# montaj_board_v2_0.net
KiCad netlist of a schematic drawn in EAGLE
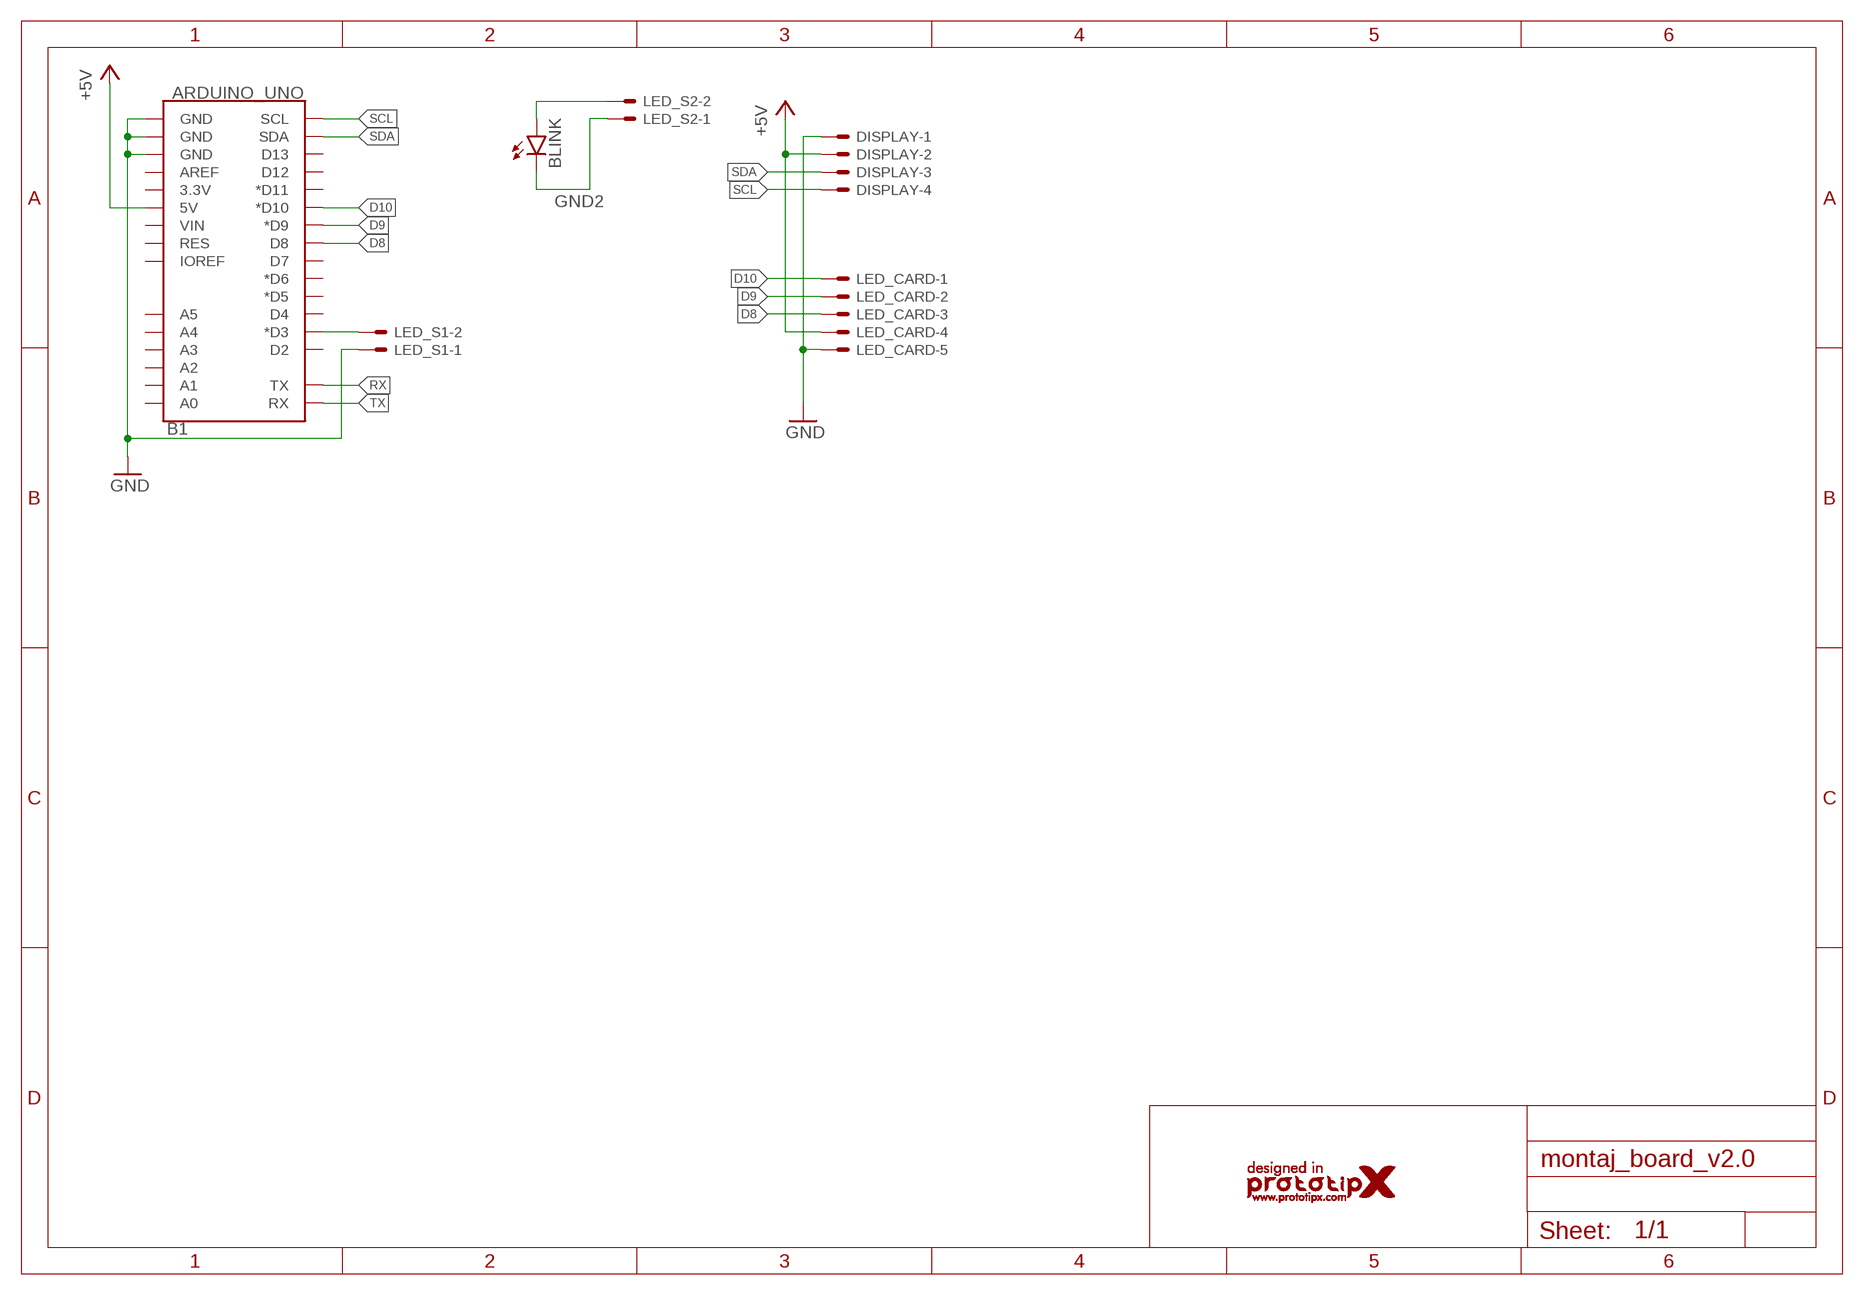
[diagram p0: schematic, sheet 1]

(export (version "E")
  (design (tool "Eeschema 10.0.6"))
  (components
    (comp (ref "B1")
      (value "ARDUINO_UNO")
      (footprint "eagle-import:UNO_R3_SHIELD")
      (libsource (lib "eagle-import") (part "ARDUINO_UNO_R3_SHIELDBASIC"))
    )
    (comp (ref "BLINK")
      (value "LED3MM")
      (footprint "eagle-import:LED3MM")
      (libsource (lib "eagle-import") (part "LED3MM"))
    )
    (comp (ref "DISPLAY")
      (value "C-GRID-04-70543")
      (footprint "eagle-import:70543-04")
      (fields (field (name "MF") "MOLEX"))
      (libsource (lib "eagle-import") (part "C-GRID-04-70543"))
    )
    (comp (ref "LED_CARD")
      (value "C-GRID-05-70543")
      (footprint "eagle-import:70543-05")
      (fields (field (name "MF") "MOLEX"))
      (libsource (lib "eagle-import") (part "C-GRID-05-70543"))
    )
    (comp (ref "LED_S1")
      (value "C-GRID-02-70543")
      (footprint "eagle-import:70543-02")
      (fields (field (name "MF") "MOLEX"))
      (libsource (lib "eagle-import") (part "C-GRID-02-70543"))
    )
    (comp (ref "LED_S2")
      (value "C-GRID-02-70543")
      (footprint "eagle-import:70543-02")
      (fields (field (name "MF") "MOLEX"))
      (libsource (lib "eagle-import") (part "C-GRID-02-70543"))
    )
    (comp (ref "LOGO1")
      (value "PROTOTIPXDESIGN")
      (footprint "eagle-import:PROTOTIPX_DESING_20MM")
      (libsource (lib "eagle-import") (part "PROTOTIPXDESIGN"))
    )
  )
  (nets
    (net (code "1") (name "+5V") (class "Default")
      (node (ref "B1") (pin "5V") (pinfunction "5V_5V") (pintype "bidirectional"))
      (node (ref "DISPLAY") (pin "2") (pinfunction "S_2") (pintype "passive"))
      (node (ref "LED_CARD") (pin "4") (pinfunction "S_4") (pintype "passive"))
    )
    (net (code "2") (name "/GND2") (class "Default")
      (node (ref "BLINK") (pin "K") (pinfunction "C_K") (pintype "passive"))
      (node (ref "LED_S2") (pin "1") (pinfunction "S_1") (pintype "passive"))
    )
    (net (code "3") (name "D8") (class "Default")
      (node (ref "B1") (pin "D8") (pinfunction "D8_D8") (pintype "bidirectional"))
      (node (ref "LED_CARD") (pin "3") (pinfunction "S_3") (pintype "passive"))
    )
    (net (code "4") (name "D9") (class "Default")
      (node (ref "B1") (pin "D9") (pinfunction "*D9_D9") (pintype "bidirectional"))
      (node (ref "LED_CARD") (pin "2") (pinfunction "S_2") (pintype "passive"))
    )
    (net (code "5") (name "D10") (class "Default")
      (node (ref "B1") (pin "D10") (pinfunction "*D10_D10") (pintype "bidirectional"))
      (node (ref "LED_CARD") (pin "1") (pinfunction "S_1") (pintype "passive"))
    )
    (net (code "6") (name "GND") (class "Default")
      (node (ref "B1") (pin "GND@0") (pinfunction "GND_GND@0") (pintype "bidirectional"))
      (node (ref "B1") (pin "GND@1") (pinfunction "GND_GND@1") (pintype "bidirectional"))
      (node (ref "B1") (pin "GND@2") (pinfunction "GND_GND@2") (pintype "bidirectional"))
      (node (ref "DISPLAY") (pin "1") (pinfunction "S_1") (pintype "passive"))
      (node (ref "LED_CARD") (pin "5") (pinfunction "S_5") (pintype "passive"))
      (node (ref "LED_S1") (pin "1") (pinfunction "S_1") (pintype "passive"))
    )
    (net (code "7") (name "Net-(B1-*D3)") (class "Default")
      (node (ref "B1") (pin "D3") (pinfunction "*D3_D3") (pintype "bidirectional"))
      (node (ref "LED_S1") (pin "2") (pinfunction "S_2") (pintype "passive"))
    )
    (net (code "8") (name "Net-(LED_S2B-S)") (class "Default")
      (node (ref "BLINK") (pin "A") (pinfunction "A_A") (pintype "passive"))
      (node (ref "LED_S2") (pin "2") (pinfunction "S_2") (pintype "passive"))
    )
    (net (code "9") (name "RX") (class "Default")
      (node (ref "B1") (pin "TX") (pinfunction "TX_TX") (pintype "bidirectional"))
    )
    (net (code "10") (name "SCL") (class "Default")
      (node (ref "B1") (pin "SCL") (pinfunction "SCL_SCL") (pintype "bidirectional"))
      (node (ref "DISPLAY") (pin "4") (pinfunction "S_4") (pintype "passive"))
    )
    (net (code "11") (name "SDA") (class "Default")
      (node (ref "B1") (pin "SDA") (pinfunction "SDA_SDA") (pintype "bidirectional"))
      (node (ref "DISPLAY") (pin "3") (pinfunction "S_3") (pintype "passive"))
    )
    (net (code "12") (name "TX") (class "Default")
      (node (ref "B1") (pin "RX") (pinfunction "RX_RX") (pintype "bidirectional"))
    )
    (net (code "13") (name "unconnected-(B1-*D5-PadD5)") (class "Default")
      (node (ref "B1") (pin "D5") (pinfunction "*D5_D5") (pintype "bidirectional"))
    )
    (net (code "14") (name "unconnected-(B1-*D6-PadD6)") (class "Default")
      (node (ref "B1") (pin "D6") (pinfunction "*D6_D6") (pintype "bidirectional"))
    )
    (net (code "15") (name "unconnected-(B1-*D11-PadD11)") (class "Default")
      (node (ref "B1") (pin "D11") (pinfunction "*D11_D11") (pintype "bidirectional"))
    )
    (net (code "16") (name "unconnected-(B1-Pad3.3V)") (class "Default")
      (node (ref "B1") (pin "3.3V") (pinfunction "3.3V_3.3V") (pintype "bidirectional"))
    )
    (net (code "17") (name "unconnected-(B1-PadA0)") (class "Default")
      (node (ref "B1") (pin "A0") (pinfunction "A0_A0") (pintype "bidirectional"))
    )
    (net (code "18") (name "unconnected-(B1-PadA1)") (class "Default")
      (node (ref "B1") (pin "A1") (pinfunction "A1_A1") (pintype "bidirectional"))
    )
    (net (code "19") (name "unconnected-(B1-PadA2)") (class "Default")
      (node (ref "B1") (pin "A2") (pinfunction "A2_A2") (pintype "bidirectional"))
    )
    (net (code "20") (name "unconnected-(B1-PadA3)") (class "Default")
      (node (ref "B1") (pin "A3") (pinfunction "A3_A3") (pintype "bidirectional"))
    )
    (net (code "21") (name "unconnected-(B1-PadA4)") (class "Default")
      (node (ref "B1") (pin "A4") (pinfunction "A4_A4") (pintype "bidirectional"))
    )
    (net (code "22") (name "unconnected-(B1-PadA5)") (class "Default")
      (node (ref "B1") (pin "A5") (pinfunction "A5_A5") (pintype "bidirectional"))
    )
    (net (code "23") (name "unconnected-(B1-PadAREF)") (class "Default")
      (node (ref "B1") (pin "AREF") (pinfunction "AREF_AREF") (pintype "bidirectional"))
    )
    (net (code "24") (name "unconnected-(B1-PadD2)") (class "Default")
      (node (ref "B1") (pin "D2") (pinfunction "D2_D2") (pintype "bidirectional"))
    )
    (net (code "25") (name "unconnected-(B1-PadD4)") (class "Default")
      (node (ref "B1") (pin "D4") (pinfunction "D4_D4") (pintype "bidirectional"))
    )
    (net (code "26") (name "unconnected-(B1-PadD7)") (class "Default")
      (node (ref "B1") (pin "D7") (pinfunction "D7_D7") (pintype "bidirectional"))
    )
    (net (code "27") (name "unconnected-(B1-PadD12)") (class "Default")
      (node (ref "B1") (pin "D12") (pinfunction "D12_D12") (pintype "bidirectional"))
    )
    (net (code "28") (name "unconnected-(B1-PadD13)") (class "Default")
      (node (ref "B1") (pin "D13") (pinfunction "D13_D13") (pintype "bidirectional"))
    )
    (net (code "29") (name "unconnected-(B1-PadIOREF)") (class "Default")
      (node (ref "B1") (pin "IOREF") (pinfunction "IOREF_IOREF") (pintype "bidirectional"))
    )
    (net (code "30") (name "unconnected-(B1-PadRES)") (class "Default")
      (node (ref "B1") (pin "RES") (pinfunction "RES_RES") (pintype "bidirectional"))
    )
    (net (code "31") (name "unconnected-(B1-PadVIN)") (class "Default")
      (node (ref "B1") (pin "VIN") (pinfunction "VIN_VIN") (pintype "bidirectional"))
    )
  )
)
